# multiSPIschematic.net
KiCad netlist of a schematic drawn in EAGLE
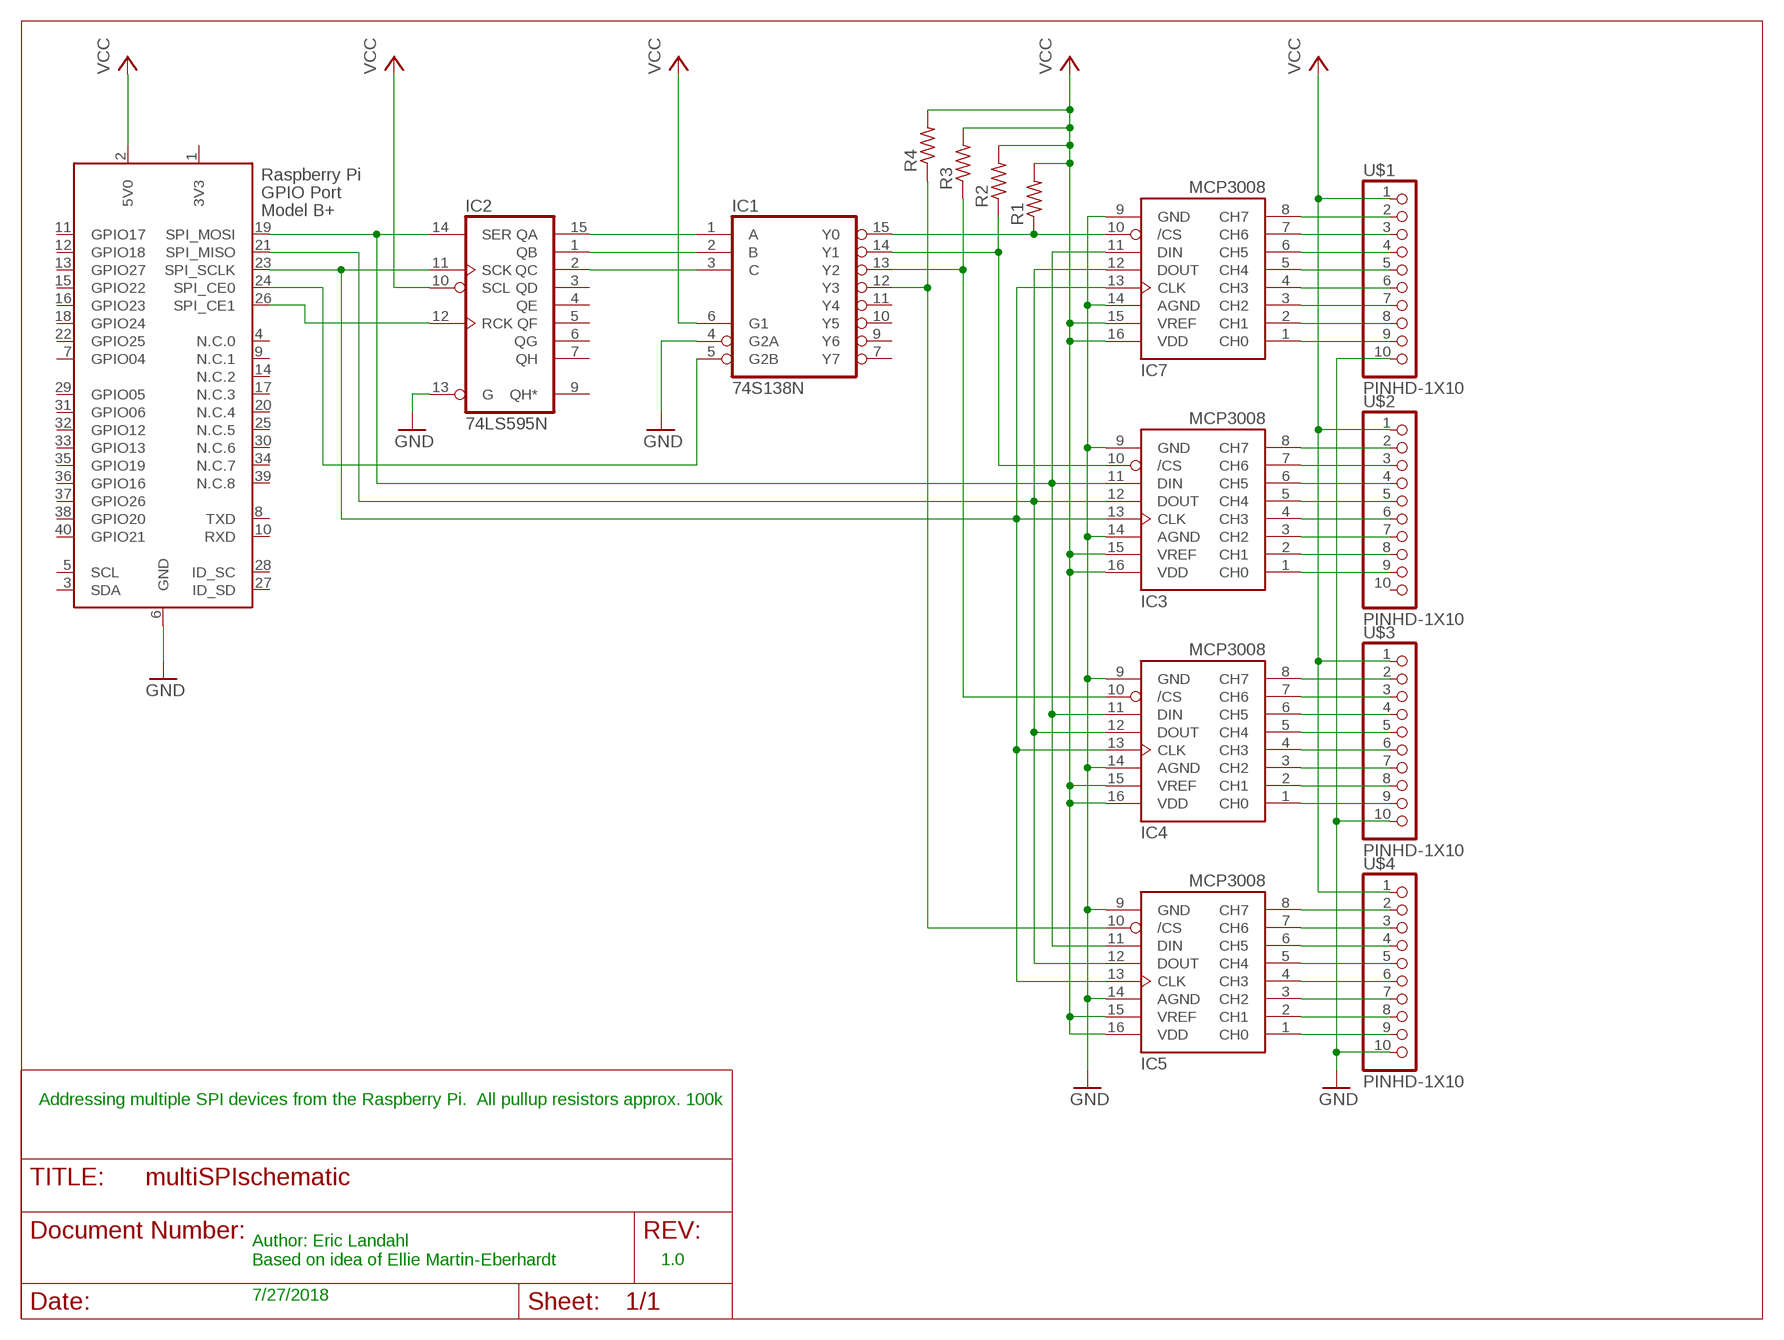
[diagram p0: schematic, sheet 1]

(export (version "E")
  (design (tool "Eeschema 10.0.6"))
  (components
    (comp (ref "IC1")
      (value "74S138N")
      (footprint "eagle-import:DIL16")
      (libsource (lib "eagle-import") (part "74138NS"))
    )
    (comp (ref "IC2")
      (value "74LS595N")
      (footprint "eagle-import:DIL16")
      (libsource (lib "eagle-import") (part "74595NLS"))
    )
    (comp (ref "IC3")
      (value "MCP3008")
      (footprint "eagle-import:DIL16")
      (libsource (lib "eagle-import") (part "MCP3008"))
    )
    (comp (ref "IC4")
      (value "MCP3008")
      (footprint "eagle-import:DIL16")
      (libsource (lib "eagle-import") (part "MCP3008"))
    )
    (comp (ref "IC5")
      (value "MCP3008")
      (footprint "eagle-import:DIL16")
      (libsource (lib "eagle-import") (part "MCP3008"))
    )
    (comp (ref "IC7")
      (value "MCP3008")
      (footprint "eagle-import:DIL16")
      (libsource (lib "eagle-import") (part "MCP3008"))
    )
    (comp (ref "R1")
      (value "R-US_0207/10")
      (footprint "eagle-import:0207_10")
      (libsource (lib "eagle-import") (part "R-US_0207/10"))
    )
    (comp (ref "R2")
      (value "R-US_0207/10")
      (footprint "eagle-import:0207_10")
      (libsource (lib "eagle-import") (part "R-US_0207/10"))
    )
    (comp (ref "R3")
      (value "R-US_0207/10")
      (footprint "eagle-import:0207_10")
      (libsource (lib "eagle-import") (part "R-US_0207/10"))
    )
    (comp (ref "R4")
      (value "R-US_0207/10")
      (footprint "eagle-import:0207_10")
      (libsource (lib "eagle-import") (part "R-US_0207/10"))
    )
    (comp (ref "U$1")
      (value "PINHD-1X10")
      (footprint "eagle-import:1X10-BIG")
      (libsource (lib "eagle-import") (part "PINHD-1X10"))
    )
    (comp (ref "U$2")
      (value "PINHD-1X10")
      (footprint "eagle-import:1X10-BIG")
      (libsource (lib "eagle-import") (part "PINHD-1X10"))
    )
    (comp (ref "U$3")
      (value "PINHD-1X10")
      (footprint "eagle-import:1X10-BIG")
      (libsource (lib "eagle-import") (part "PINHD-1X10"))
    )
    (comp (ref "U$4")
      (value "PINHD-1X10")
      (footprint "eagle-import:1X10-BIG")
      (libsource (lib "eagle-import") (part "PINHD-1X10"))
    )
    (comp (ref "X1")
      (value "RASPI_GPIO_B+_BOX")
      (footprint "eagle-import:RASPI_GPIO_B+_BOX")
      (libsource (lib "eagle-import") (part "RASPI_GPIO_B+_BOX"))
    )
  )
  (nets
    (net (code "1") (name "/3V3") (class "Default")
      (node (ref "X1") (pin "1") (pinfunction "3V3_1") (pintype "power_in"))
    )
    (net (code "2") (name "GND") (class "Default")
      (node (ref "IC1") (pin "4") (pinfunction "G2A_4") (pintype "input"))
      (node (ref "IC2") (pin "13") (pinfunction "G_13") (pintype "input"))
      (node (ref "IC3") (pin "14") (pinfunction "AGND_14") (pintype "power_in"))
      (node (ref "IC3") (pin "9") (pinfunction "GND_9") (pintype "power_in"))
      (node (ref "IC4") (pin "14") (pinfunction "AGND_14") (pintype "power_in"))
      (node (ref "IC4") (pin "9") (pinfunction "GND_9") (pintype "power_in"))
      (node (ref "IC5") (pin "14") (pinfunction "AGND_14") (pintype "power_in"))
      (node (ref "IC5") (pin "9") (pinfunction "GND_9") (pintype "power_in"))
      (node (ref "IC7") (pin "14") (pinfunction "AGND_14") (pintype "power_in"))
      (node (ref "IC7") (pin "9") (pinfunction "GND_9") (pintype "power_in"))
      (node (ref "U$1") (pin "10") (pinfunction "10_10") (pintype "passive"))
      (node (ref "U$3") (pin "10") (pinfunction "10_10") (pintype "passive"))
      (node (ref "U$4") (pin "10") (pinfunction "10_10") (pintype "passive"))
      (node (ref "X1") (pin "6") (pinfunction "GND_6") (pintype "power_in"))
    )
    (net (code "3") (name "Net-(IC1A-A)") (class "Default")
      (node (ref "IC1") (pin "1") (pinfunction "A_1") (pintype "input"))
      (node (ref "IC2") (pin "15") (pinfunction "QA_15") (pintype "tri_state"))
    )
    (net (code "4") (name "Net-(IC1A-B)") (class "Default")
      (node (ref "IC1") (pin "2") (pinfunction "B_2") (pintype "input"))
      (node (ref "IC2") (pin "1") (pinfunction "QB_1") (pintype "tri_state"))
    )
    (net (code "5") (name "Net-(IC1A-C)") (class "Default")
      (node (ref "IC1") (pin "3") (pinfunction "C_3") (pintype "input"))
      (node (ref "IC2") (pin "2") (pinfunction "QC_2") (pintype "tri_state"))
    )
    (net (code "6") (name "Net-(IC1A-G2B)") (class "Default")
      (node (ref "IC1") (pin "5") (pinfunction "G2B_5") (pintype "input"))
      (node (ref "X1") (pin "24") (pinfunction "SPI_CE0_24") (pintype "bidirectional"))
    )
    (net (code "7") (name "Net-(IC1A-Y0)") (class "Default")
      (node (ref "IC1") (pin "15") (pinfunction "Y0_15") (pintype "output"))
      (node (ref "IC7") (pin "10") (pinfunction "/CS_10") (pintype "input"))
      (node (ref "R1") (pin "1") (pinfunction "1_1") (pintype "passive"))
    )
    (net (code "8") (name "Net-(IC1A-Y1)") (class "Default")
      (node (ref "IC1") (pin "14") (pinfunction "Y1_14") (pintype "output"))
      (node (ref "IC3") (pin "10") (pinfunction "/CS_10") (pintype "input"))
      (node (ref "R2") (pin "1") (pinfunction "1_1") (pintype "passive"))
    )
    (net (code "9") (name "Net-(IC1A-Y2)") (class "Default")
      (node (ref "IC1") (pin "13") (pinfunction "Y2_13") (pintype "output"))
      (node (ref "IC4") (pin "10") (pinfunction "/CS_10") (pintype "input"))
      (node (ref "R3") (pin "1") (pinfunction "1_1") (pintype "passive"))
    )
    (net (code "10") (name "Net-(IC1A-Y3)") (class "Default")
      (node (ref "IC1") (pin "12") (pinfunction "Y3_12") (pintype "output"))
      (node (ref "IC5") (pin "10") (pinfunction "/CS_10") (pintype "input"))
      (node (ref "R4") (pin "1") (pinfunction "1_1") (pintype "passive"))
    )
    (net (code "11") (name "Net-(IC2A-RCK)") (class "Default")
      (node (ref "IC2") (pin "12") (pinfunction "RCK_12") (pintype "input"))
      (node (ref "X1") (pin "26") (pinfunction "SPI_CE1_26") (pintype "bidirectional"))
    )
    (net (code "12") (name "Net-(IC2A-SCK)") (class "Default")
      (node (ref "IC2") (pin "11") (pinfunction "SCK_11") (pintype "input"))
      (node (ref "IC3") (pin "13") (pinfunction "CLK_13") (pintype "input"))
      (node (ref "IC4") (pin "13") (pinfunction "CLK_13") (pintype "input"))
      (node (ref "IC5") (pin "13") (pinfunction "CLK_13") (pintype "input"))
      (node (ref "IC7") (pin "13") (pinfunction "CLK_13") (pintype "input"))
      (node (ref "X1") (pin "23") (pinfunction "SPI_SCLK_23") (pintype "bidirectional"))
    )
    (net (code "13") (name "Net-(IC2A-SER)") (class "Default")
      (node (ref "IC2") (pin "14") (pinfunction "SER_14") (pintype "input"))
      (node (ref "IC3") (pin "11") (pinfunction "DIN_11") (pintype "input"))
      (node (ref "IC4") (pin "11") (pinfunction "DIN_11") (pintype "input"))
      (node (ref "IC5") (pin "11") (pinfunction "DIN_11") (pintype "input"))
      (node (ref "IC7") (pin "11") (pinfunction "DIN_11") (pintype "input"))
      (node (ref "X1") (pin "19") (pinfunction "SPI_MOSI_19") (pintype "bidirectional"))
    )
    (net (code "14") (name "Net-(IC3-CH0)") (class "Default")
      (node (ref "IC3") (pin "1") (pinfunction "CH0_1") (pintype "input"))
      (node (ref "U$2") (pin "9") (pinfunction "9_9") (pintype "passive"))
    )
    (net (code "15") (name "Net-(IC3-CH1)") (class "Default")
      (node (ref "IC3") (pin "2") (pinfunction "CH1_2") (pintype "input"))
      (node (ref "U$2") (pin "8") (pinfunction "8_8") (pintype "passive"))
    )
    (net (code "16") (name "Net-(IC3-CH2)") (class "Default")
      (node (ref "IC3") (pin "3") (pinfunction "CH2_3") (pintype "input"))
      (node (ref "U$2") (pin "7") (pinfunction "7_7") (pintype "passive"))
    )
    (net (code "17") (name "Net-(IC3-CH3)") (class "Default")
      (node (ref "IC3") (pin "4") (pinfunction "CH3_4") (pintype "input"))
      (node (ref "U$2") (pin "6") (pinfunction "6_6") (pintype "passive"))
    )
    (net (code "18") (name "Net-(IC3-CH4)") (class "Default")
      (node (ref "IC3") (pin "5") (pinfunction "CH4_5") (pintype "input"))
      (node (ref "U$2") (pin "5") (pinfunction "5_5") (pintype "passive"))
    )
    (net (code "19") (name "Net-(IC3-CH5)") (class "Default")
      (node (ref "IC3") (pin "6") (pinfunction "CH5_6") (pintype "input"))
      (node (ref "U$2") (pin "4") (pinfunction "4_4") (pintype "passive"))
    )
    (net (code "20") (name "Net-(IC3-CH6)") (class "Default")
      (node (ref "IC3") (pin "7") (pinfunction "CH6_7") (pintype "input"))
      (node (ref "U$2") (pin "3") (pinfunction "3_3") (pintype "passive"))
    )
    (net (code "21") (name "Net-(IC3-CH7)") (class "Default")
      (node (ref "IC3") (pin "8") (pinfunction "CH7_8") (pintype "input"))
      (node (ref "U$2") (pin "2") (pinfunction "2_2") (pintype "passive"))
    )
    (net (code "22") (name "Net-(IC3-DOUT)") (class "Default")
      (node (ref "IC3") (pin "12") (pinfunction "DOUT_12") (pintype "output"))
      (node (ref "IC4") (pin "12") (pinfunction "DOUT_12") (pintype "output"))
      (node (ref "IC5") (pin "12") (pinfunction "DOUT_12") (pintype "output"))
      (node (ref "IC7") (pin "12") (pinfunction "DOUT_12") (pintype "output"))
      (node (ref "X1") (pin "21") (pinfunction "SPI_MISO_21") (pintype "bidirectional"))
    )
    (net (code "23") (name "Net-(IC4-CH0)") (class "Default")
      (node (ref "IC4") (pin "1") (pinfunction "CH0_1") (pintype "input"))
      (node (ref "U$3") (pin "9") (pinfunction "9_9") (pintype "passive"))
    )
    (net (code "24") (name "Net-(IC4-CH1)") (class "Default")
      (node (ref "IC4") (pin "2") (pinfunction "CH1_2") (pintype "input"))
      (node (ref "U$3") (pin "8") (pinfunction "8_8") (pintype "passive"))
    )
    (net (code "25") (name "Net-(IC4-CH2)") (class "Default")
      (node (ref "IC4") (pin "3") (pinfunction "CH2_3") (pintype "input"))
      (node (ref "U$3") (pin "7") (pinfunction "7_7") (pintype "passive"))
    )
    (net (code "26") (name "Net-(IC4-CH3)") (class "Default")
      (node (ref "IC4") (pin "4") (pinfunction "CH3_4") (pintype "input"))
      (node (ref "U$3") (pin "6") (pinfunction "6_6") (pintype "passive"))
    )
    (net (code "27") (name "Net-(IC4-CH4)") (class "Default")
      (node (ref "IC4") (pin "5") (pinfunction "CH4_5") (pintype "input"))
      (node (ref "U$3") (pin "5") (pinfunction "5_5") (pintype "passive"))
    )
    (net (code "28") (name "Net-(IC4-CH5)") (class "Default")
      (node (ref "IC4") (pin "6") (pinfunction "CH5_6") (pintype "input"))
      (node (ref "U$3") (pin "4") (pinfunction "4_4") (pintype "passive"))
    )
    (net (code "29") (name "Net-(IC4-CH6)") (class "Default")
      (node (ref "IC4") (pin "7") (pinfunction "CH6_7") (pintype "input"))
      (node (ref "U$3") (pin "3") (pinfunction "3_3") (pintype "passive"))
    )
    (net (code "30") (name "Net-(IC4-CH7)") (class "Default")
      (node (ref "IC4") (pin "8") (pinfunction "CH7_8") (pintype "input"))
      (node (ref "U$3") (pin "2") (pinfunction "2_2") (pintype "passive"))
    )
    (net (code "31") (name "Net-(IC5-CH0)") (class "Default")
      (node (ref "IC5") (pin "1") (pinfunction "CH0_1") (pintype "input"))
      (node (ref "U$4") (pin "9") (pinfunction "9_9") (pintype "passive"))
    )
    (net (code "32") (name "Net-(IC5-CH1)") (class "Default")
      (node (ref "IC5") (pin "2") (pinfunction "CH1_2") (pintype "input"))
      (node (ref "U$4") (pin "8") (pinfunction "8_8") (pintype "passive"))
    )
    (net (code "33") (name "Net-(IC5-CH2)") (class "Default")
      (node (ref "IC5") (pin "3") (pinfunction "CH2_3") (pintype "input"))
      (node (ref "U$4") (pin "7") (pinfunction "7_7") (pintype "passive"))
    )
    (net (code "34") (name "Net-(IC5-CH3)") (class "Default")
      (node (ref "IC5") (pin "4") (pinfunction "CH3_4") (pintype "input"))
      (node (ref "U$4") (pin "6") (pinfunction "6_6") (pintype "passive"))
    )
    (net (code "35") (name "Net-(IC5-CH4)") (class "Default")
      (node (ref "IC5") (pin "5") (pinfunction "CH4_5") (pintype "input"))
      (node (ref "U$4") (pin "5") (pinfunction "5_5") (pintype "passive"))
    )
    (net (code "36") (name "Net-(IC5-CH5)") (class "Default")
      (node (ref "IC5") (pin "6") (pinfunction "CH5_6") (pintype "input"))
      (node (ref "U$4") (pin "4") (pinfunction "4_4") (pintype "passive"))
    )
    (net (code "37") (name "Net-(IC5-CH6)") (class "Default")
      (node (ref "IC5") (pin "7") (pinfunction "CH6_7") (pintype "input"))
      (node (ref "U$4") (pin "3") (pinfunction "3_3") (pintype "passive"))
    )
    (net (code "38") (name "Net-(IC5-CH7)") (class "Default")
      (node (ref "IC5") (pin "8") (pinfunction "CH7_8") (pintype "input"))
      (node (ref "U$4") (pin "2") (pinfunction "2_2") (pintype "passive"))
    )
    (net (code "39") (name "Net-(IC7-CH0)") (class "Default")
      (node (ref "IC7") (pin "1") (pinfunction "CH0_1") (pintype "input"))
      (node (ref "U$1") (pin "9") (pinfunction "9_9") (pintype "passive"))
    )
    (net (code "40") (name "Net-(IC7-CH1)") (class "Default")
      (node (ref "IC7") (pin "2") (pinfunction "CH1_2") (pintype "input"))
      (node (ref "U$1") (pin "8") (pinfunction "8_8") (pintype "passive"))
    )
    (net (code "41") (name "Net-(IC7-CH2)") (class "Default")
      (node (ref "IC7") (pin "3") (pinfunction "CH2_3") (pintype "input"))
      (node (ref "U$1") (pin "7") (pinfunction "7_7") (pintype "passive"))
    )
    (net (code "42") (name "Net-(IC7-CH3)") (class "Default")
      (node (ref "IC7") (pin "4") (pinfunction "CH3_4") (pintype "input"))
      (node (ref "U$1") (pin "6") (pinfunction "6_6") (pintype "passive"))
    )
    (net (code "43") (name "Net-(IC7-CH4)") (class "Default")
      (node (ref "IC7") (pin "5") (pinfunction "CH4_5") (pintype "input"))
      (node (ref "U$1") (pin "5") (pinfunction "5_5") (pintype "passive"))
    )
    (net (code "44") (name "Net-(IC7-CH5)") (class "Default")
      (node (ref "IC7") (pin "6") (pinfunction "CH5_6") (pintype "input"))
      (node (ref "U$1") (pin "4") (pinfunction "4_4") (pintype "passive"))
    )
    (net (code "45") (name "Net-(IC7-CH6)") (class "Default")
      (node (ref "IC7") (pin "7") (pinfunction "CH6_7") (pintype "input"))
      (node (ref "U$1") (pin "3") (pinfunction "3_3") (pintype "passive"))
    )
    (net (code "46") (name "Net-(IC7-CH7)") (class "Default")
      (node (ref "IC7") (pin "8") (pinfunction "CH7_8") (pintype "input"))
      (node (ref "U$1") (pin "2") (pinfunction "2_2") (pintype "passive"))
    )
    (net (code "47") (name "VCC") (class "Default")
      (node (ref "IC1") (pin "6") (pinfunction "G1_6") (pintype "input"))
      (node (ref "IC2") (pin "10") (pinfunction "SCL_10") (pintype "input"))
      (node (ref "IC3") (pin "15") (pinfunction "VREF_15") (pintype "input"))
      (node (ref "IC3") (pin "16") (pinfunction "VDD_16") (pintype "power_in"))
      (node (ref "IC4") (pin "15") (pinfunction "VREF_15") (pintype "input"))
      (node (ref "IC4") (pin "16") (pinfunction "VDD_16") (pintype "power_in"))
      (node (ref "IC5") (pin "15") (pinfunction "VREF_15") (pintype "input"))
      (node (ref "IC5") (pin "16") (pinfunction "VDD_16") (pintype "power_in"))
      (node (ref "IC7") (pin "15") (pinfunction "VREF_15") (pintype "input"))
      (node (ref "IC7") (pin "16") (pinfunction "VDD_16") (pintype "power_in"))
      (node (ref "R1") (pin "2") (pinfunction "2_2") (pintype "passive"))
      (node (ref "R2") (pin "2") (pinfunction "2_2") (pintype "passive"))
      (node (ref "R3") (pin "2") (pinfunction "2_2") (pintype "passive"))
      (node (ref "R4") (pin "2") (pinfunction "2_2") (pintype "passive"))
      (node (ref "U$1") (pin "1") (pinfunction "1_1") (pintype "passive"))
      (node (ref "U$2") (pin "1") (pinfunction "1_1") (pintype "passive"))
      (node (ref "U$3") (pin "1") (pinfunction "1_1") (pintype "passive"))
      (node (ref "U$4") (pin "1") (pinfunction "1_1") (pintype "passive"))
      (node (ref "X1") (pin "2") (pinfunction "5V0_2") (pintype "power_in"))
    )
    (net (code "48") (name "unconnected-(IC1A-Y4-Pad11)") (class "Default")
      (node (ref "IC1") (pin "11") (pinfunction "Y4_11") (pintype "output"))
    )
    (net (code "49") (name "unconnected-(IC1A-Y5-Pad10)") (class "Default")
      (node (ref "IC1") (pin "10") (pinfunction "Y5_10") (pintype "output"))
    )
    (net (code "50") (name "unconnected-(IC1A-Y6-Pad9)") (class "Default")
      (node (ref "IC1") (pin "9") (pinfunction "Y6_9") (pintype "output"))
    )
    (net (code "51") (name "unconnected-(IC1A-Y7-Pad7)") (class "Default")
      (node (ref "IC1") (pin "7") (pinfunction "Y7_7") (pintype "output"))
    )
    (net (code "52") (name "unconnected-(IC2A-QD-Pad3)") (class "Default")
      (node (ref "IC2") (pin "3") (pinfunction "QD_3") (pintype "tri_state"))
    )
    (net (code "53") (name "unconnected-(IC2A-QE-Pad4)") (class "Default")
      (node (ref "IC2") (pin "4") (pinfunction "QE_4") (pintype "tri_state"))
    )
    (net (code "54") (name "unconnected-(IC2A-QF-Pad5)") (class "Default")
      (node (ref "IC2") (pin "5") (pinfunction "QF_5") (pintype "tri_state"))
    )
    (net (code "55") (name "unconnected-(IC2A-QG-Pad6)") (class "Default")
      (node (ref "IC2") (pin "6") (pinfunction "QG_6") (pintype "tri_state"))
    )
    (net (code "56") (name "unconnected-(IC2A-QH*-Pad9)") (class "Default")
      (node (ref "IC2") (pin "9") (pinfunction "QH*_9") (pintype "tri_state"))
    )
    (net (code "57") (name "unconnected-(IC2A-QH-Pad7)") (class "Default")
      (node (ref "IC2") (pin "7") (pinfunction "QH_7") (pintype "tri_state"))
    )
    (net (code "58") (name "unconnected-(U$2-Pad10)") (class "Default")
      (node (ref "U$2") (pin "10") (pinfunction "10_10") (pintype "passive"))
    )
    (net (code "59") (name "unconnected-(X1-GPIO04-Pad7)") (class "Default")
      (node (ref "X1") (pin "7") (pinfunction "GPIO04_7") (pintype "bidirectional"))
    )
    (net (code "60") (name "unconnected-(X1-GPIO05-Pad29)") (class "Default")
      (node (ref "X1") (pin "29") (pinfunction "GPIO05_29") (pintype "no_connect"))
    )
    (net (code "61") (name "unconnected-(X1-GPIO06-Pad31)") (class "Default")
      (node (ref "X1") (pin "31") (pinfunction "GPIO06_31") (pintype "no_connect"))
    )
    (net (code "62") (name "unconnected-(X1-GPIO12-Pad32)") (class "Default")
      (node (ref "X1") (pin "32") (pinfunction "GPIO12_32") (pintype "no_connect"))
    )
    (net (code "63") (name "unconnected-(X1-GPIO13-Pad33)") (class "Default")
      (node (ref "X1") (pin "33") (pinfunction "GPIO13_33") (pintype "no_connect"))
    )
    (net (code "64") (name "unconnected-(X1-GPIO16-Pad36)") (class "Default")
      (node (ref "X1") (pin "36") (pinfunction "GPIO16_36") (pintype "no_connect"))
    )
    (net (code "65") (name "unconnected-(X1-GPIO17-Pad11)") (class "Default")
      (node (ref "X1") (pin "11") (pinfunction "GPIO17_11") (pintype "bidirectional"))
    )
    (net (code "66") (name "unconnected-(X1-GPIO18-Pad12)") (class "Default")
      (node (ref "X1") (pin "12") (pinfunction "GPIO18_12") (pintype "bidirectional"))
    )
    (net (code "67") (name "unconnected-(X1-GPIO19-Pad35)") (class "Default")
      (node (ref "X1") (pin "35") (pinfunction "GPIO19_35") (pintype "no_connect"))
    )
    (net (code "68") (name "unconnected-(X1-GPIO20-Pad38)") (class "Default")
      (node (ref "X1") (pin "38") (pinfunction "GPIO20_38") (pintype "no_connect"))
    )
    (net (code "69") (name "unconnected-(X1-GPIO21-Pad40)") (class "Default")
      (node (ref "X1") (pin "40") (pinfunction "GPIO21_40") (pintype "no_connect"))
    )
    (net (code "70") (name "unconnected-(X1-GPIO22-Pad15)") (class "Default")
      (node (ref "X1") (pin "15") (pinfunction "GPIO22_15") (pintype "bidirectional"))
    )
    (net (code "71") (name "unconnected-(X1-GPIO23-Pad16)") (class "Default")
      (node (ref "X1") (pin "16") (pinfunction "GPIO23_16") (pintype "bidirectional"))
    )
    (net (code "72") (name "unconnected-(X1-GPIO24-Pad18)") (class "Default")
      (node (ref "X1") (pin "18") (pinfunction "GPIO24_18") (pintype "bidirectional"))
    )
    (net (code "73") (name "unconnected-(X1-GPIO25-Pad22)") (class "Default")
      (node (ref "X1") (pin "22") (pinfunction "GPIO25_22") (pintype "bidirectional"))
    )
    (net (code "74") (name "unconnected-(X1-GPIO26-Pad37)") (class "Default")
      (node (ref "X1") (pin "37") (pinfunction "GPIO26_37") (pintype "no_connect"))
    )
    (net (code "75") (name "unconnected-(X1-GPIO27-Pad13)") (class "Default")
      (node (ref "X1") (pin "13") (pinfunction "GPIO27_13") (pintype "bidirectional"))
    )
    (net (code "76") (name "unconnected-(X1-ID_SC-Pad28)") (class "Default")
      (node (ref "X1") (pin "28") (pinfunction "ID_SC_28") (pintype "no_connect"))
    )
    (net (code "77") (name "unconnected-(X1-ID_SD-Pad27)") (class "Default")
      (node (ref "X1") (pin "27") (pinfunction "ID_SD_27") (pintype "no_connect"))
    )
    (net (code "78") (name "unconnected-(X1-N.C.0-Pad4)") (class "Default")
      (node (ref "X1") (pin "4") (pinfunction "N.C.0_4") (pintype "no_connect"))
    )
    (net (code "79") (name "unconnected-(X1-N.C.1-Pad9)") (class "Default")
      (node (ref "X1") (pin "9") (pinfunction "N.C.1_9") (pintype "no_connect"))
    )
    (net (code "80") (name "unconnected-(X1-N.C.2-Pad14)") (class "Default")
      (node (ref "X1") (pin "14") (pinfunction "N.C.2_14") (pintype "no_connect"))
    )
    (net (code "81") (name "unconnected-(X1-N.C.3-Pad17)") (class "Default")
      (node (ref "X1") (pin "17") (pinfunction "N.C.3_17") (pintype "no_connect"))
    )
    (net (code "82") (name "unconnected-(X1-N.C.4-Pad20)") (class "Default")
      (node (ref "X1") (pin "20") (pinfunction "N.C.4_20") (pintype "no_connect"))
    )
    (net (code "83") (name "unconnected-(X1-N.C.5-Pad25)") (class "Default")
      (node (ref "X1") (pin "25") (pinfunction "N.C.5_25") (pintype "no_connect"))
    )
    (net (code "84") (name "unconnected-(X1-N.C.6-Pad30)") (class "Default")
      (node (ref "X1") (pin "30") (pinfunction "N.C.6_30") (pintype "no_connect"))
    )
    (net (code "85") (name "unconnected-(X1-N.C.7-Pad34)") (class "Default")
      (node (ref "X1") (pin "34") (pinfunction "N.C.7_34") (pintype "no_connect"))
    )
    (net (code "86") (name "unconnected-(X1-N.C.8-Pad39)") (class "Default")
      (node (ref "X1") (pin "39") (pinfunction "N.C.8_39") (pintype "no_connect"))
    )
    (net (code "87") (name "unconnected-(X1-RXD-Pad10)") (class "Default")
      (node (ref "X1") (pin "10") (pinfunction "RXD_10") (pintype "bidirectional"))
    )
    (net (code "88") (name "unconnected-(X1-SCL-Pad5)") (class "Default")
      (node (ref "X1") (pin "5") (pinfunction "SCL_5") (pintype "bidirectional"))
    )
    (net (code "89") (name "unconnected-(X1-SDA-Pad3)") (class "Default")
      (node (ref "X1") (pin "3") (pinfunction "SDA_3") (pintype "bidirectional"))
    )
    (net (code "90") (name "unconnected-(X1-TXD-Pad8)") (class "Default")
      (node (ref "X1") (pin "8") (pinfunction "TXD_8") (pintype "bidirectional"))
    )
  )
)
